# rasp_sheild_ADC.net
KiCad netlist of a schematic drawn in Altium Designer
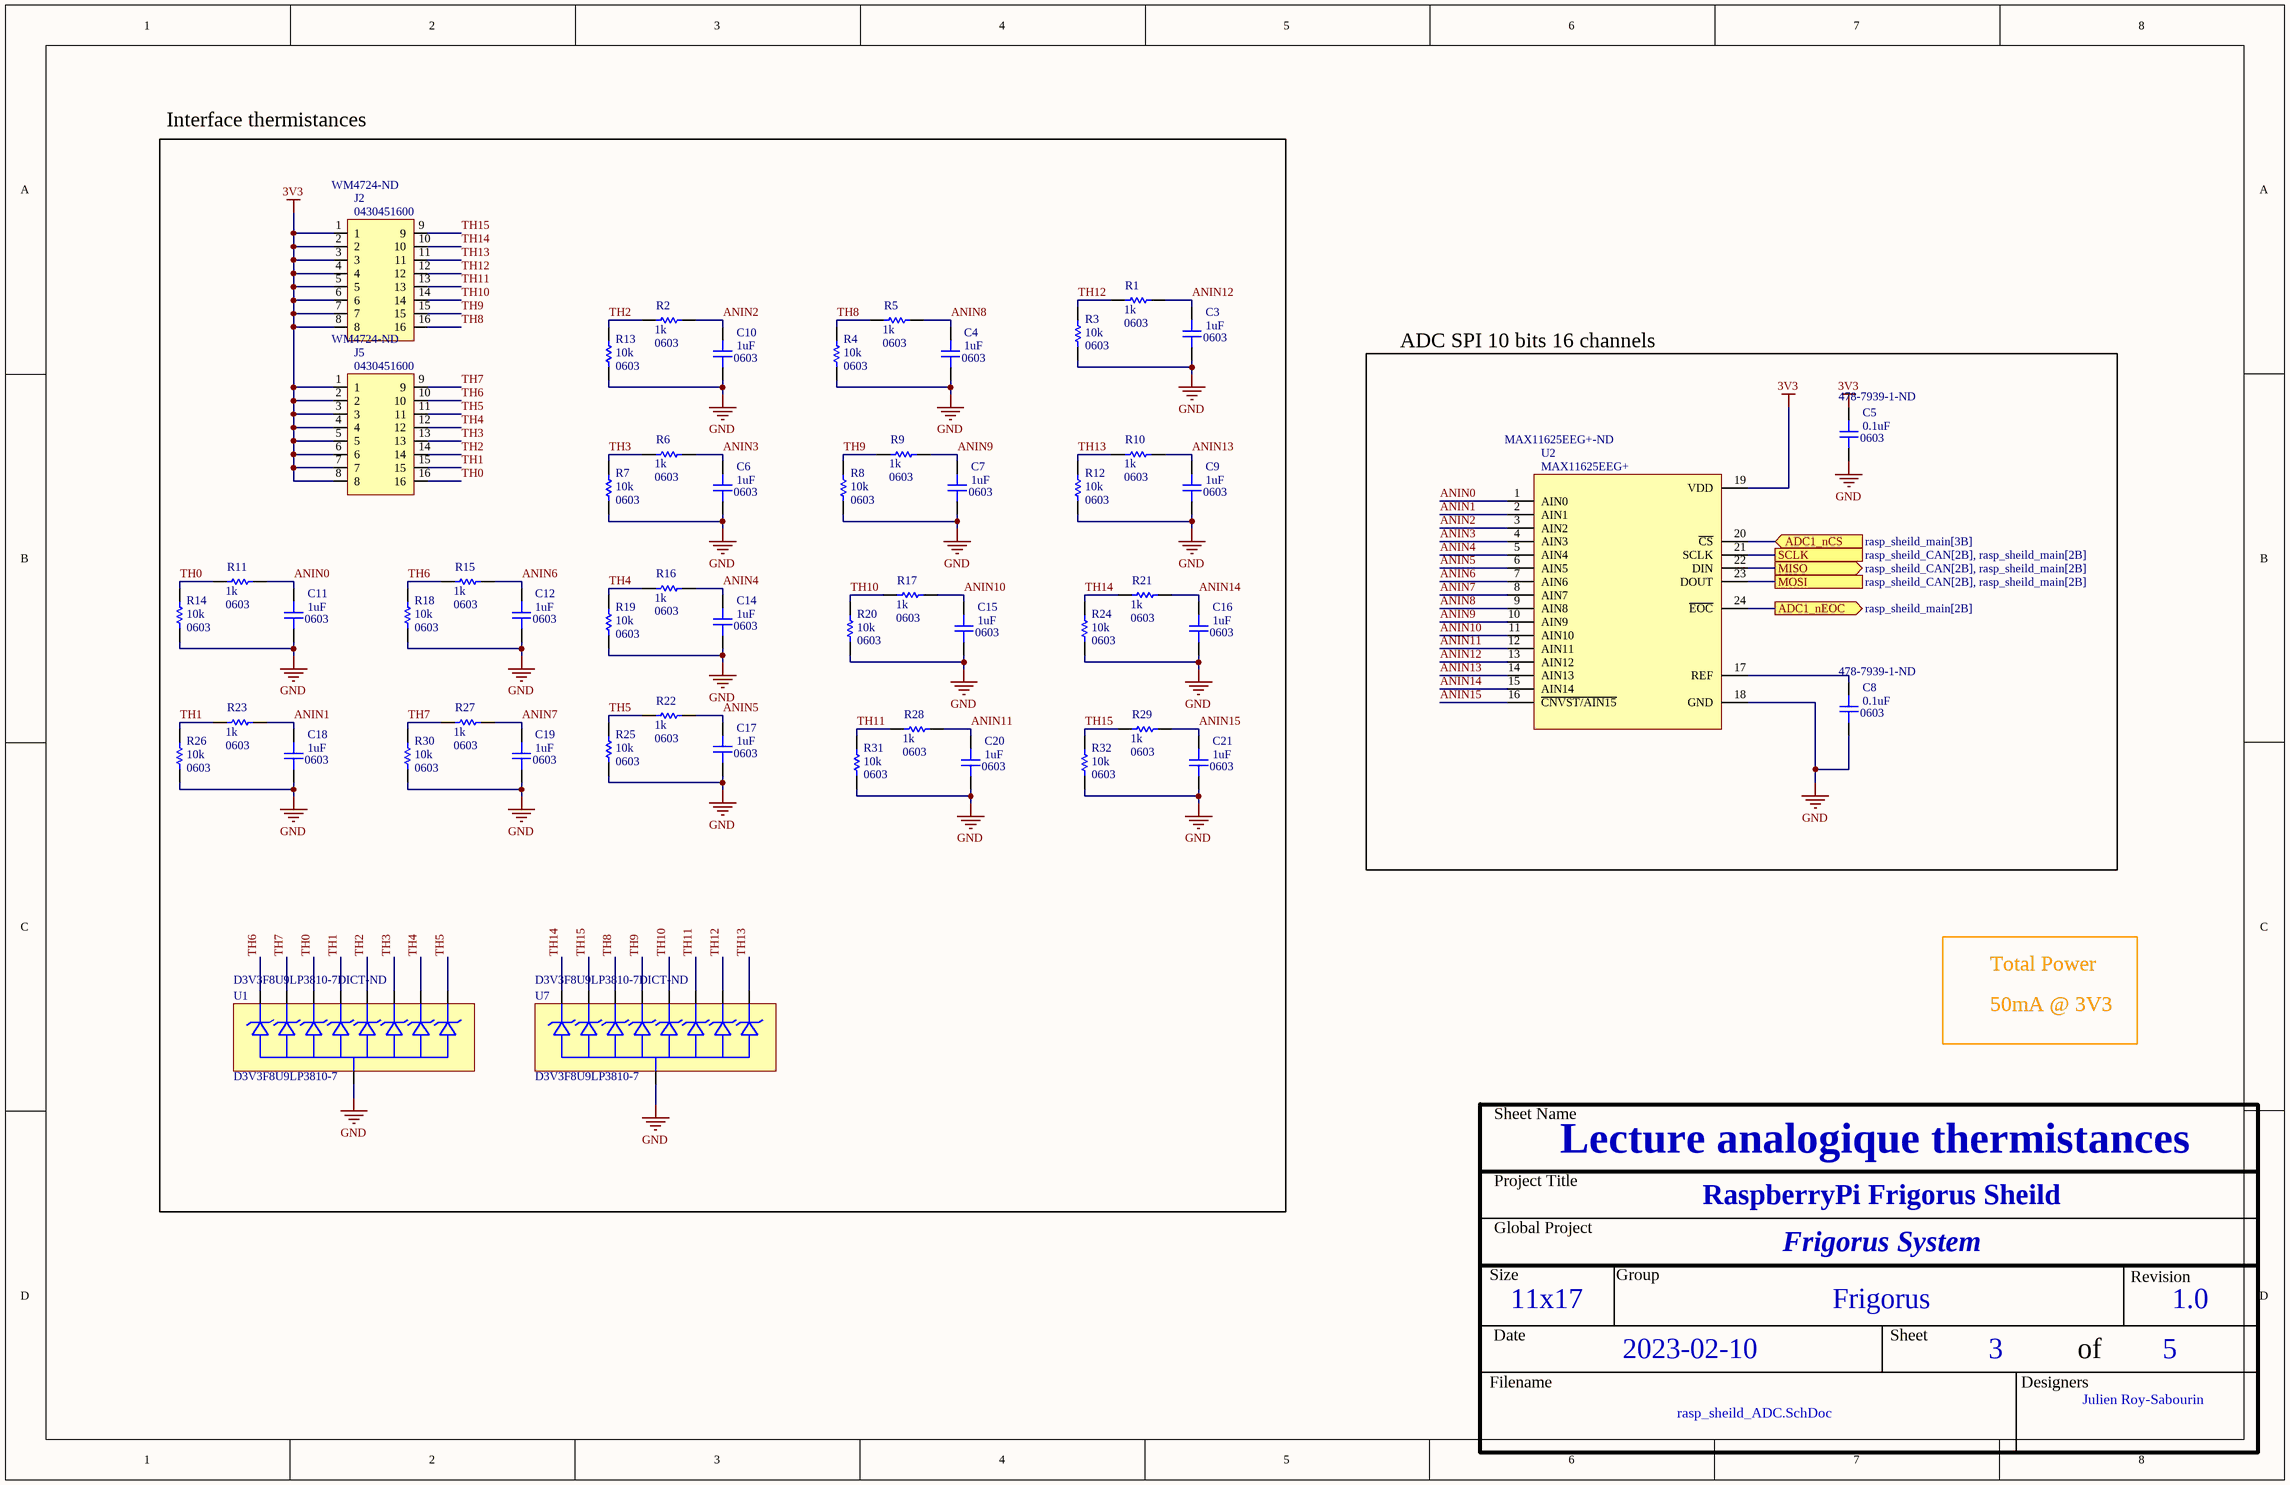
[diagram p0: rasp_sheild_ADC.SchDoc]

(export (version "E")
  (design (tool "Eeschema 10.0.6"))
  (components
    (comp (ref "C3")
      (value "1uF")
      (footprint "CAP_0603")
      (description "XXX - Description - Package")
      (fields (field (name "PACKAGE") "0603") (field (name "Comment") "Part Number"))
      (libsource (lib "royj1311") (part "CAP_0603"))
    )
    (comp (ref "C4")
      (value "1uF")
      (footprint "CAP_0603")
      (description "XXX - Description - Package")
      (fields (field (name "PACKAGE") "0603") (field (name "Comment") "Part Number"))
      (libsource (lib "royj1311") (part "CAP_0603"))
    )
    (comp (ref "C5")
      (value "0.1uF")
      (footprint "CAP_0603")
      (description "XXX - Description - Package")
      (fields
        (field (name "PACKAGE") "0603")
        (field (name "SUPPLIER PART NUMBER 1") "478-7939-1-ND")
        (field (name "Comment") "Part Number")
      )
      (libsource (lib "royj1311") (part "CAP_0603"))
    )
    (comp (ref "C6")
      (value "1uF")
      (footprint "CAP_0603")
      (description "XXX - Description - Package")
      (fields (field (name "PACKAGE") "0603") (field (name "Comment") "Part Number"))
      (libsource (lib "royj1311") (part "CAP_0603"))
    )
    (comp (ref "C7")
      (value "1uF")
      (footprint "CAP_0603")
      (description "XXX - Description - Package")
      (fields (field (name "PACKAGE") "0603") (field (name "Comment") "Part Number"))
      (libsource (lib "royj1311") (part "CAP_0603"))
    )
    (comp (ref "C8")
      (value "0.1uF")
      (footprint "CAP_0603")
      (description "XXX - Description - Package")
      (fields
        (field (name "PACKAGE") "0603")
        (field (name "SUPPLIER PART NUMBER 1") "478-7939-1-ND")
        (field (name "Comment") "Part Number")
      )
      (libsource (lib "royj1311") (part "CAP_0603"))
    )
    (comp (ref "C9")
      (value "1uF")
      (footprint "CAP_0603")
      (description "XXX - Description - Package")
      (fields (field (name "PACKAGE") "0603") (field (name "Comment") "Part Number"))
      (libsource (lib "royj1311") (part "CAP_0603"))
    )
    (comp (ref "C10")
      (value "1uF")
      (footprint "CAP_0603")
      (description "XXX - Description - Package")
      (fields (field (name "PACKAGE") "0603") (field (name "Comment") "Part Number"))
      (libsource (lib "royj1311") (part "CAP_0603"))
    )
    (comp (ref "C11")
      (value "1uF")
      (footprint "CAP_0603")
      (description "XXX - Description - Package")
      (fields (field (name "PACKAGE") "0603") (field (name "Comment") "Part Number"))
      (libsource (lib "royj1311") (part "CAP_0603"))
    )
    (comp (ref "C12")
      (value "1uF")
      (footprint "CAP_0603")
      (description "XXX - Description - Package")
      (fields (field (name "PACKAGE") "0603") (field (name "Comment") "Part Number"))
      (libsource (lib "royj1311") (part "CAP_0603"))
    )
    (comp (ref "C14")
      (value "1uF")
      (footprint "CAP_0603")
      (description "XXX - Description - Package")
      (fields (field (name "PACKAGE") "0603") (field (name "Comment") "Part Number"))
      (libsource (lib "royj1311") (part "CAP_0603"))
    )
    (comp (ref "C15")
      (value "1uF")
      (footprint "CAP_0603")
      (description "XXX - Description - Package")
      (fields (field (name "PACKAGE") "0603") (field (name "Comment") "Part Number"))
      (libsource (lib "royj1311") (part "CAP_0603"))
    )
    (comp (ref "C16")
      (value "1uF")
      (footprint "CAP_0603")
      (description "XXX - Description - Package")
      (fields (field (name "PACKAGE") "0603") (field (name "Comment") "Part Number"))
      (libsource (lib "royj1311") (part "CAP_0603"))
    )
    (comp (ref "C17")
      (value "1uF")
      (footprint "CAP_0603")
      (description "XXX - Description - Package")
      (fields (field (name "PACKAGE") "0603") (field (name "Comment") "Part Number"))
      (libsource (lib "royj1311") (part "CAP_0603"))
    )
    (comp (ref "C18")
      (value "1uF")
      (footprint "CAP_0603")
      (description "XXX - Description - Package")
      (fields (field (name "PACKAGE") "0603") (field (name "Comment") "Part Number"))
      (libsource (lib "royj1311") (part "CAP_0603"))
    )
    (comp (ref "C19")
      (value "1uF")
      (footprint "CAP_0603")
      (description "XXX - Description - Package")
      (fields (field (name "PACKAGE") "0603") (field (name "Comment") "Part Number"))
      (libsource (lib "royj1311") (part "CAP_0603"))
    )
    (comp (ref "C20")
      (value "1uF")
      (footprint "CAP_0603")
      (description "XXX - Description - Package")
      (fields (field (name "PACKAGE") "0603") (field (name "Comment") "Part Number"))
      (libsource (lib "royj1311") (part "CAP_0603"))
    )
    (comp (ref "C21")
      (value "1uF")
      (footprint "CAP_0603")
      (description "XXX - Description - Package")
      (fields (field (name "PACKAGE") "0603") (field (name "Comment") "Part Number"))
      (libsource (lib "royj1311") (part "CAP_0603"))
    )
    (comp (ref "J2")
      (value "0430451600")
      (footprint "0430451600")
      (description "Connector Header Through Hole, Right Angle 16 position 0.118\" (3.00mm)")
      (fields (field (name "SUPPLIER PART NUMBER 1") "WM4724-ND"))
      (libsource (lib "royj1311") (part "0430451600"))
    )
    (comp (ref "J5")
      (value "0430451600")
      (footprint "0430451600")
      (description "Connector Header Through Hole, Right Angle 16 position 0.118\" (3.00mm)")
      (fields (field (name "SUPPLIER PART NUMBER 1") "WM4724-ND"))
      (libsource (lib "royj1311") (part "0430451600"))
    )
    (comp (ref "R1")
      (value "1k")
      (footprint "RES_0603")
      (description "XXX - Description - Package")
      (fields (field (name "PACKAGE") "0603") (field (name "Comment") "Part Number"))
      (libsource (lib "royj1311") (part "RES_0603"))
    )
    (comp (ref "R2")
      (value "1k")
      (footprint "RES_0603")
      (description "XXX - Description - Package")
      (fields (field (name "PACKAGE") "0603") (field (name "Comment") "Part Number"))
      (libsource (lib "royj1311") (part "RES_0603"))
    )
    (comp (ref "R3")
      (value "10k")
      (footprint "RES_0603")
      (description "XXX - Description - Package")
      (fields (field (name "PACKAGE") "0603") (field (name "Comment") "Part Number"))
      (libsource (lib "royj1311") (part "RES_0603"))
    )
    (comp (ref "R4")
      (value "10k")
      (footprint "RES_0603")
      (description "XXX - Description - Package")
      (fields (field (name "PACKAGE") "0603") (field (name "Comment") "Part Number"))
      (libsource (lib "royj1311") (part "RES_0603"))
    )
    (comp (ref "R5")
      (value "1k")
      (footprint "RES_0603")
      (description "XXX - Description - Package")
      (fields (field (name "PACKAGE") "0603") (field (name "Comment") "Part Number"))
      (libsource (lib "royj1311") (part "RES_0603"))
    )
    (comp (ref "R6")
      (value "1k")
      (footprint "RES_0603")
      (description "XXX - Description - Package")
      (fields (field (name "PACKAGE") "0603") (field (name "Comment") "Part Number"))
      (libsource (lib "royj1311") (part "RES_0603"))
    )
    (comp (ref "R7")
      (value "10k")
      (footprint "RES_0603")
      (description "XXX - Description - Package")
      (fields (field (name "PACKAGE") "0603") (field (name "Comment") "Part Number"))
      (libsource (lib "royj1311") (part "RES_0603"))
    )
    (comp (ref "R8")
      (value "10k")
      (footprint "RES_0603")
      (description "XXX - Description - Package")
      (fields (field (name "PACKAGE") "0603") (field (name "Comment") "Part Number"))
      (libsource (lib "royj1311") (part "RES_0603"))
    )
    (comp (ref "R9")
      (value "1k")
      (footprint "RES_0603")
      (description "XXX - Description - Package")
      (fields (field (name "PACKAGE") "0603") (field (name "Comment") "Part Number"))
      (libsource (lib "royj1311") (part "RES_0603"))
    )
    (comp (ref "R10")
      (value "1k")
      (footprint "RES_0603")
      (description "XXX - Description - Package")
      (fields (field (name "PACKAGE") "0603") (field (name "Comment") "Part Number"))
      (libsource (lib "royj1311") (part "RES_0603"))
    )
    (comp (ref "R11")
      (value "1k")
      (footprint "RES_0603")
      (description "XXX - Description - Package")
      (fields (field (name "PACKAGE") "0603") (field (name "Comment") "Part Number"))
      (libsource (lib "royj1311") (part "RES_0603"))
    )
    (comp (ref "R12")
      (value "10k")
      (footprint "RES_0603")
      (description "XXX - Description - Package")
      (fields (field (name "PACKAGE") "0603") (field (name "Comment") "Part Number"))
      (libsource (lib "royj1311") (part "RES_0603"))
    )
    (comp (ref "R13")
      (value "10k")
      (footprint "RES_0603")
      (description "XXX - Description - Package")
      (fields (field (name "PACKAGE") "0603") (field (name "Comment") "Part Number"))
      (libsource (lib "royj1311") (part "RES_0603"))
    )
    (comp (ref "R14")
      (value "10k")
      (footprint "RES_0603")
      (description "XXX - Description - Package")
      (fields (field (name "PACKAGE") "0603") (field (name "Comment") "Part Number"))
      (libsource (lib "royj1311") (part "RES_0603"))
    )
    (comp (ref "R15")
      (value "1k")
      (footprint "RES_0603")
      (description "XXX - Description - Package")
      (fields (field (name "PACKAGE") "0603") (field (name "Comment") "Part Number"))
      (libsource (lib "royj1311") (part "RES_0603"))
    )
    (comp (ref "R16")
      (value "1k")
      (footprint "RES_0603")
      (description "XXX - Description - Package")
      (fields (field (name "PACKAGE") "0603") (field (name "Comment") "Part Number"))
      (libsource (lib "royj1311") (part "RES_0603"))
    )
    (comp (ref "R17")
      (value "1k")
      (footprint "RES_0603")
      (description "XXX - Description - Package")
      (fields (field (name "PACKAGE") "0603") (field (name "Comment") "Part Number"))
      (libsource (lib "royj1311") (part "RES_0603"))
    )
    (comp (ref "R18")
      (value "10k")
      (footprint "RES_0603")
      (description "XXX - Description - Package")
      (fields (field (name "PACKAGE") "0603") (field (name "Comment") "Part Number"))
      (libsource (lib "royj1311") (part "RES_0603"))
    )
    (comp (ref "R19")
      (value "10k")
      (footprint "RES_0603")
      (description "XXX - Description - Package")
      (fields (field (name "PACKAGE") "0603") (field (name "Comment") "Part Number"))
      (libsource (lib "royj1311") (part "RES_0603"))
    )
    (comp (ref "R20")
      (value "10k")
      (footprint "RES_0603")
      (description "XXX - Description - Package")
      (fields (field (name "PACKAGE") "0603") (field (name "Comment") "Part Number"))
      (libsource (lib "royj1311") (part "RES_0603"))
    )
    (comp (ref "R21")
      (value "1k")
      (footprint "RES_0603")
      (description "XXX - Description - Package")
      (fields (field (name "PACKAGE") "0603") (field (name "Comment") "Part Number"))
      (libsource (lib "royj1311") (part "RES_0603"))
    )
    (comp (ref "R22")
      (value "1k")
      (footprint "RES_0603")
      (description "XXX - Description - Package")
      (fields (field (name "PACKAGE") "0603") (field (name "Comment") "Part Number"))
      (libsource (lib "royj1311") (part "RES_0603"))
    )
    (comp (ref "R23")
      (value "1k")
      (footprint "RES_0603")
      (description "XXX - Description - Package")
      (fields (field (name "PACKAGE") "0603") (field (name "Comment") "Part Number"))
      (libsource (lib "royj1311") (part "RES_0603"))
    )
    (comp (ref "R24")
      (value "10k")
      (footprint "RES_0603")
      (description "XXX - Description - Package")
      (fields (field (name "PACKAGE") "0603") (field (name "Comment") "Part Number"))
      (libsource (lib "royj1311") (part "RES_0603"))
    )
    (comp (ref "R25")
      (value "10k")
      (footprint "RES_0603")
      (description "XXX - Description - Package")
      (fields (field (name "PACKAGE") "0603") (field (name "Comment") "Part Number"))
      (libsource (lib "royj1311") (part "RES_0603"))
    )
    (comp (ref "R26")
      (value "10k")
      (footprint "RES_0603")
      (description "XXX - Description - Package")
      (fields (field (name "PACKAGE") "0603") (field (name "Comment") "Part Number"))
      (libsource (lib "royj1311") (part "RES_0603"))
    )
    (comp (ref "R27")
      (value "1k")
      (footprint "RES_0603")
      (description "XXX - Description - Package")
      (fields (field (name "PACKAGE") "0603") (field (name "Comment") "Part Number"))
      (libsource (lib "royj1311") (part "RES_0603"))
    )
    (comp (ref "R28")
      (value "1k")
      (footprint "RES_0603")
      (description "XXX - Description - Package")
      (fields (field (name "PACKAGE") "0603") (field (name "Comment") "Part Number"))
      (libsource (lib "royj1311") (part "RES_0603"))
    )
    (comp (ref "R29")
      (value "1k")
      (footprint "RES_0603")
      (description "XXX - Description - Package")
      (fields (field (name "PACKAGE") "0603") (field (name "Comment") "Part Number"))
      (libsource (lib "royj1311") (part "RES_0603"))
    )
    (comp (ref "R30")
      (value "10k")
      (footprint "RES_0603")
      (description "XXX - Description - Package")
      (fields (field (name "PACKAGE") "0603") (field (name "Comment") "Part Number"))
      (libsource (lib "royj1311") (part "RES_0603"))
    )
    (comp (ref "R31")
      (value "10k")
      (footprint "RES_0603")
      (description "XXX - Description - Package")
      (fields (field (name "PACKAGE") "0603") (field (name "Comment") "Part Number"))
      (libsource (lib "royj1311") (part "RES_0603"))
    )
    (comp (ref "R32")
      (value "10k")
      (footprint "RES_0603")
      (description "XXX - Description - Package")
      (fields (field (name "PACKAGE") "0603") (field (name "Comment") "Part Number"))
      (libsource (lib "royj1311") (part "RES_0603"))
    )
    (comp (ref "U1")
      (value "D3V3F8U9LP3810-7")
      (footprint "D3V3F8U9LP3810-7")
      (description "5V (Typ) Clamp 5A (8/20µs) Ipp Tvs Diode Surface Mount U-DFN3810-9 (Type B)")
      (fields (field (name "SUPPLIER PART NUMBER 1") "D3V3F8U9LP3810-7DICT-ND"))
      (libsource (lib "royj1311") (part "D3V3F8U9LP3810-7"))
    )
    (comp (ref "U2")
      (value "MAX11625EEG+")
      (footprint "24-QSSOP")
      (description "10 Bit Analog to Digital Converter 16 Input 1 SAR 24-QSOP")
      (fields (field (name "SUPPLIER PART NUMBER 1") "MAX11625EEG+-ND"))
      (libsource (lib "royj1311") (part "MAX11625EEG+"))
    )
    (comp (ref "U7")
      (value "D3V3F8U9LP3810-7")
      (footprint "D3V3F8U9LP3810-7")
      (description "5V (Typ) Clamp 5A (8/20µs) Ipp Tvs Diode Surface Mount U-DFN3810-9 (Type B)")
      (fields (field (name "SUPPLIER PART NUMBER 1") "D3V3F8U9LP3810-7DICT-ND"))
      (libsource (lib "royj1311") (part "D3V3F8U9LP3810-7"))
    )
  )
  (nets
    (net (code "1") (name "/ADC1_nCS") (class "Default")
      (node (ref "U2") (pin "20") (pinfunction "~{CS}_20") (pintype "passive"))
    )
    (net (code "2") (name "/ADC1_nEOC") (class "Default")
      (node (ref "U2") (pin "24") (pinfunction "~{EOC}_24") (pintype "passive"))
    )
    (net (code "3") (name "/ANIN0") (class "Default")
      (node (ref "C11") (pin "2") (pinfunction "2_2") (pintype "passive"))
      (node (ref "R11") (pin "1") (pinfunction "1_1") (pintype "passive"))
      (node (ref "U2") (pin "1") (pinfunction "AIN0_1") (pintype "passive"))
    )
    (net (code "4") (name "/ANIN1") (class "Default")
      (node (ref "C18") (pin "2") (pinfunction "2_2") (pintype "passive"))
      (node (ref "R23") (pin "1") (pinfunction "1_1") (pintype "passive"))
      (node (ref "U2") (pin "2") (pinfunction "AIN1_2") (pintype "passive"))
    )
    (net (code "5") (name "/ANIN2") (class "Default")
      (node (ref "C10") (pin "2") (pinfunction "2_2") (pintype "passive"))
      (node (ref "R2") (pin "1") (pinfunction "1_1") (pintype "passive"))
      (node (ref "U2") (pin "3") (pinfunction "AIN2_3") (pintype "passive"))
    )
    (net (code "6") (name "/ANIN3") (class "Default")
      (node (ref "C6") (pin "2") (pinfunction "2_2") (pintype "passive"))
      (node (ref "R6") (pin "1") (pinfunction "1_1") (pintype "passive"))
      (node (ref "U2") (pin "4") (pinfunction "AIN3_4") (pintype "passive"))
    )
    (net (code "7") (name "/ANIN4") (class "Default")
      (node (ref "C14") (pin "2") (pinfunction "2_2") (pintype "passive"))
      (node (ref "R16") (pin "1") (pinfunction "1_1") (pintype "passive"))
      (node (ref "U2") (pin "5") (pinfunction "AIN4_5") (pintype "passive"))
    )
    (net (code "8") (name "/ANIN5") (class "Default")
      (node (ref "C17") (pin "2") (pinfunction "2_2") (pintype "passive"))
      (node (ref "R22") (pin "1") (pinfunction "1_1") (pintype "passive"))
      (node (ref "U2") (pin "6") (pinfunction "AIN5_6") (pintype "passive"))
    )
    (net (code "9") (name "/ANIN6") (class "Default")
      (node (ref "C12") (pin "2") (pinfunction "2_2") (pintype "passive"))
      (node (ref "R15") (pin "1") (pinfunction "1_1") (pintype "passive"))
      (node (ref "U2") (pin "7") (pinfunction "AIN6_7") (pintype "passive"))
    )
    (net (code "10") (name "/ANIN7") (class "Default")
      (node (ref "C19") (pin "2") (pinfunction "2_2") (pintype "passive"))
      (node (ref "R27") (pin "1") (pinfunction "1_1") (pintype "passive"))
      (node (ref "U2") (pin "8") (pinfunction "AIN7_8") (pintype "passive"))
    )
    (net (code "11") (name "/ANIN8") (class "Default")
      (node (ref "C4") (pin "2") (pinfunction "2_2") (pintype "passive"))
      (node (ref "R5") (pin "1") (pinfunction "1_1") (pintype "passive"))
      (node (ref "U2") (pin "9") (pinfunction "AIN8_9") (pintype "passive"))
    )
    (net (code "12") (name "/ANIN9") (class "Default")
      (node (ref "C7") (pin "2") (pinfunction "2_2") (pintype "passive"))
      (node (ref "R9") (pin "1") (pinfunction "1_1") (pintype "passive"))
      (node (ref "U2") (pin "10") (pinfunction "AIN9_10") (pintype "passive"))
    )
    (net (code "13") (name "/ANIN10") (class "Default")
      (node (ref "C15") (pin "2") (pinfunction "2_2") (pintype "passive"))
      (node (ref "R17") (pin "1") (pinfunction "1_1") (pintype "passive"))
      (node (ref "U2") (pin "11") (pinfunction "AIN10_11") (pintype "passive"))
    )
    (net (code "14") (name "/ANIN11") (class "Default")
      (node (ref "C20") (pin "2") (pinfunction "2_2") (pintype "passive"))
      (node (ref "R28") (pin "1") (pinfunction "1_1") (pintype "passive"))
      (node (ref "U2") (pin "12") (pinfunction "AIN11_12") (pintype "passive"))
    )
    (net (code "15") (name "/ANIN12") (class "Default")
      (node (ref "C3") (pin "2") (pinfunction "2_2") (pintype "passive"))
      (node (ref "R1") (pin "1") (pinfunction "1_1") (pintype "passive"))
      (node (ref "U2") (pin "13") (pinfunction "AIN12_13") (pintype "passive"))
    )
    (net (code "16") (name "/ANIN13") (class "Default")
      (node (ref "C9") (pin "2") (pinfunction "2_2") (pintype "passive"))
      (node (ref "R10") (pin "1") (pinfunction "1_1") (pintype "passive"))
      (node (ref "U2") (pin "14") (pinfunction "AIN13_14") (pintype "passive"))
    )
    (net (code "17") (name "/ANIN14") (class "Default")
      (node (ref "C16") (pin "2") (pinfunction "2_2") (pintype "passive"))
      (node (ref "R21") (pin "1") (pinfunction "1_1") (pintype "passive"))
      (node (ref "U2") (pin "15") (pinfunction "AIN14_15") (pintype "passive"))
    )
    (net (code "18") (name "/ANIN15") (class "Default")
      (node (ref "C21") (pin "2") (pinfunction "2_2") (pintype "passive"))
      (node (ref "R29") (pin "1") (pinfunction "1_1") (pintype "passive"))
      (node (ref "U2") (pin "16") (pinfunction "~{CNVST/AIN15}_16") (pintype "passive"))
    )
    (net (code "19") (name "/MISO") (class "Default")
      (node (ref "U2") (pin "22") (pinfunction "DIN_22") (pintype "passive"))
    )
    (net (code "20") (name "/MOSI") (class "Default")
      (node (ref "U2") (pin "23") (pinfunction "DOUT_23") (pintype "passive"))
    )
    (net (code "21") (name "/SCLK") (class "Default")
      (node (ref "U2") (pin "21") (pinfunction "SCLK_21") (pintype "passive"))
    )
    (net (code "22") (name "/TH0") (class "Default")
      (node (ref "J5") (pin "16") (pinfunction "16_16") (pintype "passive"))
      (node (ref "R11") (pin "2") (pinfunction "2_2") (pintype "passive"))
      (node (ref "R14") (pin "1") (pinfunction "1_1") (pintype "passive"))
      (node (ref "U1") (pin "4") (pinfunction "4_4") (pintype "passive"))
    )
    (net (code "23") (name "/TH1") (class "Default")
      (node (ref "J5") (pin "15") (pinfunction "15_15") (pintype "passive"))
      (node (ref "R23") (pin "2") (pinfunction "2_2") (pintype "passive"))
      (node (ref "R26") (pin "1") (pinfunction "1_1") (pintype "passive"))
      (node (ref "U1") (pin "5") (pinfunction "5_5") (pintype "passive"))
    )
    (net (code "24") (name "/TH2") (class "Default")
      (node (ref "J5") (pin "14") (pinfunction "14_14") (pintype "passive"))
      (node (ref "R13") (pin "1") (pinfunction "1_1") (pintype "passive"))
      (node (ref "R2") (pin "2") (pinfunction "2_2") (pintype "passive"))
      (node (ref "U1") (pin "6") (pinfunction "6_6") (pintype "passive"))
    )
    (net (code "25") (name "/TH3") (class "Default")
      (node (ref "J5") (pin "13") (pinfunction "13_13") (pintype "passive"))
      (node (ref "R6") (pin "2") (pinfunction "2_2") (pintype "passive"))
      (node (ref "R7") (pin "1") (pinfunction "1_1") (pintype "passive"))
      (node (ref "U1") (pin "7") (pinfunction "7_7") (pintype "passive"))
    )
    (net (code "26") (name "/TH4") (class "Default")
      (node (ref "J5") (pin "12") (pinfunction "12_12") (pintype "passive"))
      (node (ref "R16") (pin "2") (pinfunction "2_2") (pintype "passive"))
      (node (ref "R19") (pin "1") (pinfunction "1_1") (pintype "passive"))
      (node (ref "U1") (pin "8") (pinfunction "8_8") (pintype "passive"))
    )
    (net (code "27") (name "/TH5") (class "Default")
      (node (ref "J5") (pin "11") (pinfunction "11_11") (pintype "passive"))
      (node (ref "R22") (pin "2") (pinfunction "2_2") (pintype "passive"))
      (node (ref "R25") (pin "1") (pinfunction "1_1") (pintype "passive"))
      (node (ref "U1") (pin "9") (pinfunction "9_9") (pintype "passive"))
    )
    (net (code "28") (name "/TH6") (class "Default")
      (node (ref "J5") (pin "10") (pinfunction "10_10") (pintype "passive"))
      (node (ref "R15") (pin "2") (pinfunction "2_2") (pintype "passive"))
      (node (ref "R18") (pin "1") (pinfunction "1_1") (pintype "passive"))
      (node (ref "U1") (pin "1") (pinfunction "1_1") (pintype "passive"))
    )
    (net (code "29") (name "/TH7") (class "Default")
      (node (ref "J5") (pin "9") (pinfunction "9_9") (pintype "passive"))
      (node (ref "R27") (pin "2") (pinfunction "2_2") (pintype "passive"))
      (node (ref "R30") (pin "1") (pinfunction "1_1") (pintype "passive"))
      (node (ref "U1") (pin "2") (pinfunction "2_2") (pintype "passive"))
    )
    (net (code "30") (name "/TH8") (class "Default")
      (node (ref "J2") (pin "16") (pinfunction "16_16") (pintype "passive"))
      (node (ref "R4") (pin "1") (pinfunction "1_1") (pintype "passive"))
      (node (ref "R5") (pin "2") (pinfunction "2_2") (pintype "passive"))
      (node (ref "U7") (pin "4") (pinfunction "4_4") (pintype "passive"))
    )
    (net (code "31") (name "/TH9") (class "Default")
      (node (ref "J2") (pin "15") (pinfunction "15_15") (pintype "passive"))
      (node (ref "R8") (pin "1") (pinfunction "1_1") (pintype "passive"))
      (node (ref "R9") (pin "2") (pinfunction "2_2") (pintype "passive"))
      (node (ref "U7") (pin "5") (pinfunction "5_5") (pintype "passive"))
    )
    (net (code "32") (name "/TH10") (class "Default")
      (node (ref "J2") (pin "14") (pinfunction "14_14") (pintype "passive"))
      (node (ref "R17") (pin "2") (pinfunction "2_2") (pintype "passive"))
      (node (ref "R20") (pin "1") (pinfunction "1_1") (pintype "passive"))
      (node (ref "U7") (pin "6") (pinfunction "6_6") (pintype "passive"))
    )
    (net (code "33") (name "/TH11") (class "Default")
      (node (ref "J2") (pin "13") (pinfunction "13_13") (pintype "passive"))
      (node (ref "R28") (pin "2") (pinfunction "2_2") (pintype "passive"))
      (node (ref "R31") (pin "1") (pinfunction "1_1") (pintype "passive"))
      (node (ref "U7") (pin "7") (pinfunction "7_7") (pintype "passive"))
    )
    (net (code "34") (name "/TH12") (class "Default")
      (node (ref "J2") (pin "12") (pinfunction "12_12") (pintype "passive"))
      (node (ref "R1") (pin "2") (pinfunction "2_2") (pintype "passive"))
      (node (ref "R3") (pin "1") (pinfunction "1_1") (pintype "passive"))
      (node (ref "U7") (pin "8") (pinfunction "8_8") (pintype "passive"))
    )
    (net (code "35") (name "/TH13") (class "Default")
      (node (ref "J2") (pin "11") (pinfunction "11_11") (pintype "passive"))
      (node (ref "R10") (pin "2") (pinfunction "2_2") (pintype "passive"))
      (node (ref "R12") (pin "1") (pinfunction "1_1") (pintype "passive"))
      (node (ref "U7") (pin "9") (pinfunction "9_9") (pintype "passive"))
    )
    (net (code "36") (name "/TH14") (class "Default")
      (node (ref "J2") (pin "10") (pinfunction "10_10") (pintype "passive"))
      (node (ref "R21") (pin "2") (pinfunction "2_2") (pintype "passive"))
      (node (ref "R24") (pin "1") (pinfunction "1_1") (pintype "passive"))
      (node (ref "U7") (pin "1") (pinfunction "1_1") (pintype "passive"))
    )
    (net (code "37") (name "/TH15") (class "Default")
      (node (ref "J2") (pin "9") (pinfunction "9_9") (pintype "passive"))
      (node (ref "R29") (pin "2") (pinfunction "2_2") (pintype "passive"))
      (node (ref "R32") (pin "1") (pinfunction "1_1") (pintype "passive"))
      (node (ref "U7") (pin "2") (pinfunction "2_2") (pintype "passive"))
    )
    (net (code "38") (name "3V3") (class "Default")
      (node (ref "C5") (pin "2") (pinfunction "2_2") (pintype "passive"))
      (node (ref "J2") (pin "1") (pinfunction "1_1") (pintype "passive"))
      (node (ref "J2") (pin "2") (pinfunction "2_2") (pintype "passive"))
      (node (ref "J2") (pin "3") (pinfunction "3_3") (pintype "passive"))
      (node (ref "J2") (pin "4") (pinfunction "4_4") (pintype "passive"))
      (node (ref "J2") (pin "5") (pinfunction "5_5") (pintype "passive"))
      (node (ref "J2") (pin "6") (pinfunction "6_6") (pintype "passive"))
      (node (ref "J2") (pin "7") (pinfunction "7_7") (pintype "passive"))
      (node (ref "J2") (pin "8") (pinfunction "8_8") (pintype "passive"))
      (node (ref "J5") (pin "1") (pinfunction "1_1") (pintype "passive"))
      (node (ref "J5") (pin "2") (pinfunction "2_2") (pintype "passive"))
      (node (ref "J5") (pin "3") (pinfunction "3_3") (pintype "passive"))
      (node (ref "J5") (pin "4") (pinfunction "4_4") (pintype "passive"))
      (node (ref "J5") (pin "5") (pinfunction "5_5") (pintype "passive"))
      (node (ref "J5") (pin "6") (pinfunction "6_6") (pintype "passive"))
      (node (ref "J5") (pin "7") (pinfunction "7_7") (pintype "passive"))
      (node (ref "J5") (pin "8") (pinfunction "8_8") (pintype "passive"))
      (node (ref "U2") (pin "19") (pinfunction "VDD_19") (pintype "power_in"))
    )
    (net (code "39") (name "GND") (class "Default")
      (node (ref "C10") (pin "1") (pinfunction "1_1") (pintype "passive"))
      (node (ref "C11") (pin "1") (pinfunction "1_1") (pintype "passive"))
      (node (ref "C12") (pin "1") (pinfunction "1_1") (pintype "passive"))
      (node (ref "C14") (pin "1") (pinfunction "1_1") (pintype "passive"))
      (node (ref "C15") (pin "1") (pinfunction "1_1") (pintype "passive"))
      (node (ref "C16") (pin "1") (pinfunction "1_1") (pintype "passive"))
      (node (ref "C17") (pin "1") (pinfunction "1_1") (pintype "passive"))
      (node (ref "C18") (pin "1") (pinfunction "1_1") (pintype "passive"))
      (node (ref "C19") (pin "1") (pinfunction "1_1") (pintype "passive"))
      (node (ref "C20") (pin "1") (pinfunction "1_1") (pintype "passive"))
      (node (ref "C21") (pin "1") (pinfunction "1_1") (pintype "passive"))
      (node (ref "C3") (pin "1") (pinfunction "1_1") (pintype "passive"))
      (node (ref "C4") (pin "1") (pinfunction "1_1") (pintype "passive"))
      (node (ref "C5") (pin "1") (pinfunction "1_1") (pintype "passive"))
      (node (ref "C6") (pin "1") (pinfunction "1_1") (pintype "passive"))
      (node (ref "C7") (pin "1") (pinfunction "1_1") (pintype "passive"))
      (node (ref "C8") (pin "1") (pinfunction "1_1") (pintype "passive"))
      (node (ref "C9") (pin "1") (pinfunction "1_1") (pintype "passive"))
      (node (ref "R12") (pin "2") (pinfunction "2_2") (pintype "passive"))
      (node (ref "R13") (pin "2") (pinfunction "2_2") (pintype "passive"))
      (node (ref "R14") (pin "2") (pinfunction "2_2") (pintype "passive"))
      (node (ref "R18") (pin "2") (pinfunction "2_2") (pintype "passive"))
      (node (ref "R19") (pin "2") (pinfunction "2_2") (pintype "passive"))
      (node (ref "R20") (pin "2") (pinfunction "2_2") (pintype "passive"))
      (node (ref "R24") (pin "2") (pinfunction "2_2") (pintype "passive"))
      (node (ref "R25") (pin "2") (pinfunction "2_2") (pintype "passive"))
      (node (ref "R26") (pin "2") (pinfunction "2_2") (pintype "passive"))
      (node (ref "R3") (pin "2") (pinfunction "2_2") (pintype "passive"))
      (node (ref "R30") (pin "2") (pinfunction "2_2") (pintype "passive"))
      (node (ref "R31") (pin "2") (pinfunction "2_2") (pintype "passive"))
      (node (ref "R32") (pin "2") (pinfunction "2_2") (pintype "passive"))
      (node (ref "R4") (pin "2") (pinfunction "2_2") (pintype "passive"))
      (node (ref "R7") (pin "2") (pinfunction "2_2") (pintype "passive"))
      (node (ref "R8") (pin "2") (pinfunction "2_2") (pintype "passive"))
      (node (ref "U1") (pin "3") (pinfunction "3_3") (pintype "passive"))
      (node (ref "U2") (pin "18") (pinfunction "GND_18") (pintype "power_in"))
      (node (ref "U7") (pin "3") (pinfunction "3_3") (pintype "passive"))
    )
    (net (code "40") (name "Net-(U2-REF)") (class "Default")
      (node (ref "C8") (pin "2") (pinfunction "2_2") (pintype "passive"))
      (node (ref "U2") (pin "17") (pinfunction "REF_17") (pintype "passive"))
    )
  )
)
